# 05_LMS7002M_RF.net
KiCad netlist of a schematic drawn in Altium Designer
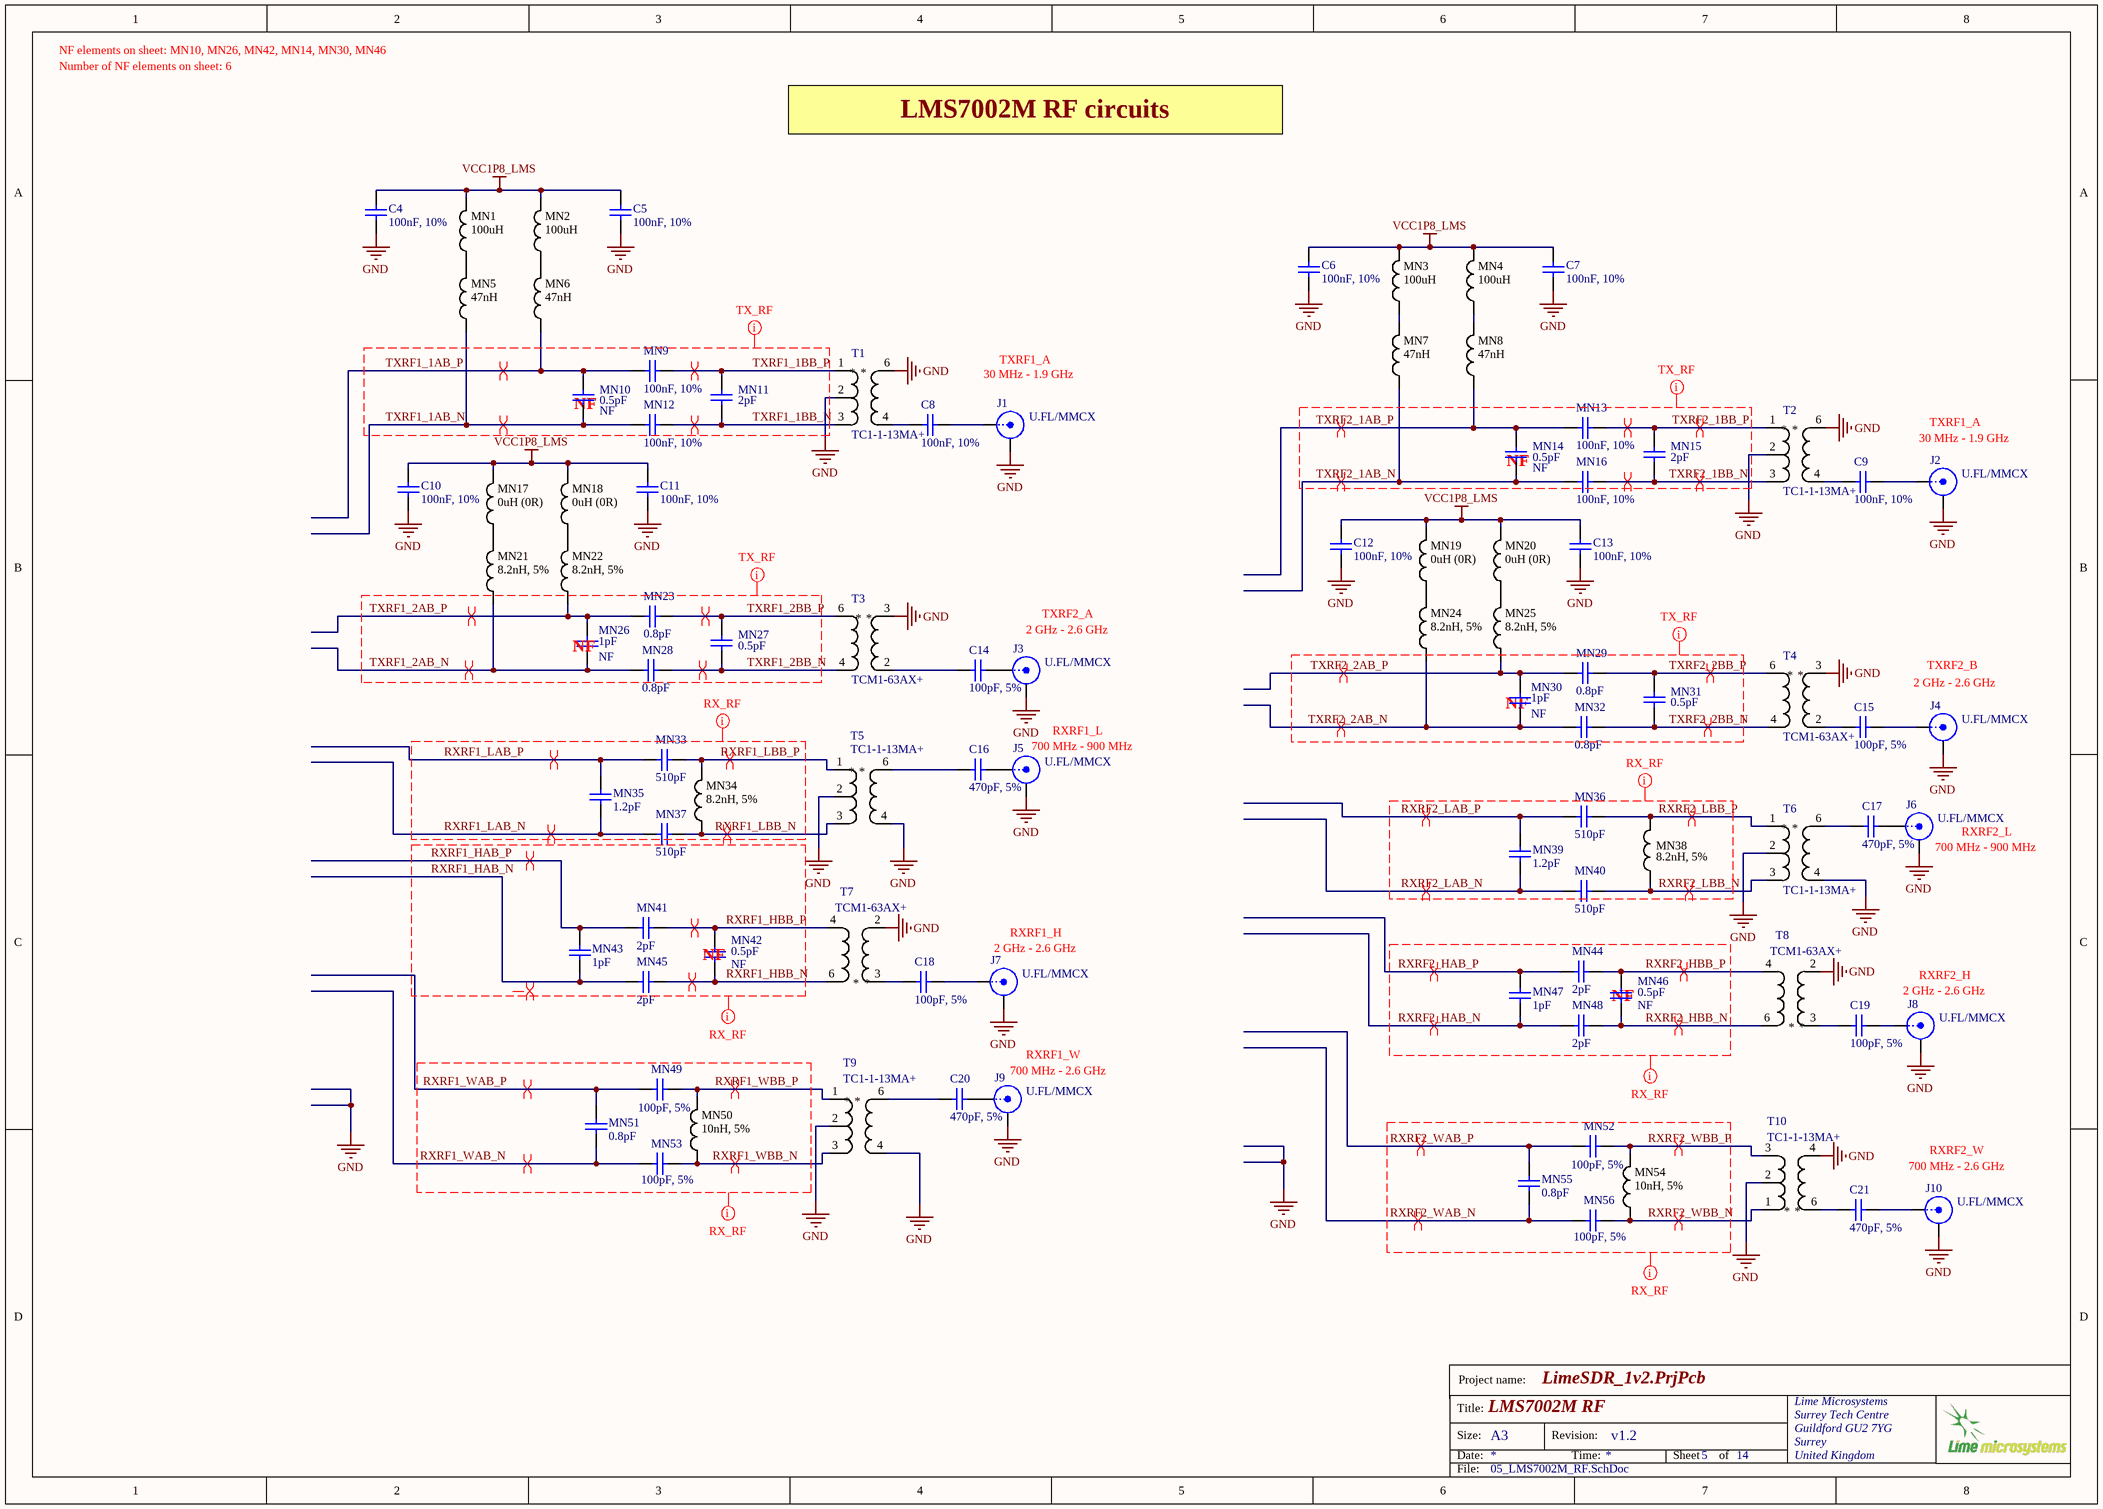
[diagram p0: 05_LMS7002M_RF.SchDoc]

(export (version "E")
  (design (tool "Eeschema 10.0.6"))
  (components
    (comp (ref "C4")
      (value "100nF, 10%")
      (footprint "CAP0402")
      (fields
        (field (name "MANUFACTURER") "Murata Electronics")
        (field (name "TOLERANCE") "10 %")
        (field (name "MANUFACTURER PART NUMBER") "GRM155R71C104KA88D")
      )
      (libsource (lib "LimeMicroAltiumLib_schLib") (part "Cap_0402"))
    )
    (comp (ref "C5")
      (value "100nF, 10%")
      (footprint "CAP0402")
      (fields
        (field (name "MANUFACTURER") "Murata Electronics")
        (field (name "TOLERANCE") "10 %")
        (field (name "MANUFACTURER PART NUMBER") "GRM155R71C104KA88D")
      )
      (libsource (lib "LimeMicroAltiumLib_schLib") (part "Cap_0402"))
    )
    (comp (ref "C6")
      (value "100nF, 10%")
      (footprint "CAP0402")
      (fields
        (field (name "MANUFACTURER") "Murata Electronics")
        (field (name "TOLERANCE") "10 %")
        (field (name "MANUFACTURER PART NUMBER") "GRM155R71C104KA88D")
      )
      (libsource (lib "LimeMicroAltiumLib_schLib") (part "Cap_0402"))
    )
    (comp (ref "C7")
      (value "100nF, 10%")
      (footprint "CAP0402")
      (fields
        (field (name "MANUFACTURER") "Murata Electronics")
        (field (name "TOLERANCE") "10 %")
        (field (name "MANUFACTURER PART NUMBER") "GRM155R71C104KA88D")
      )
      (libsource (lib "LimeMicroAltiumLib_schLib") (part "Cap_0402"))
    )
    (comp (ref "C8")
      (value "100nF, 10%")
      (footprint "CAP0402")
      (fields
        (field (name "MANUFACTURER") "Murata Electronics")
        (field (name "TOLERANCE") "10 %")
        (field (name "MANUFACTURER PART NUMBER") "GRM155R71C104KA88D")
      )
      (libsource (lib "LimeMicroAltiumLib_schLib") (part "Cap_0402"))
    )
    (comp (ref "C9")
      (value "100nF, 10%")
      (footprint "CAP0402")
      (fields
        (field (name "MANUFACTURER") "Murata Electronics")
        (field (name "TOLERANCE") "10 %")
        (field (name "MANUFACTURER PART NUMBER") "GRM155R71C104KA88D")
      )
      (libsource (lib "LimeMicroAltiumLib_schLib") (part "Cap_0402"))
    )
    (comp (ref "C10")
      (value "100nF, 10%")
      (footprint "CAP0402")
      (fields
        (field (name "MANUFACTURER") "Murata Electronics")
        (field (name "TOLERANCE") "10 %")
        (field (name "MANUFACTURER PART NUMBER") "GRM155R71C104KA88D")
      )
      (libsource (lib "LimeMicroAltiumLib_schLib") (part "Cap_0402"))
    )
    (comp (ref "C11")
      (value "100nF, 10%")
      (footprint "CAP0402")
      (fields
        (field (name "MANUFACTURER") "Murata Electronics")
        (field (name "TOLERANCE") "10 %")
        (field (name "MANUFACTURER PART NUMBER") "GRM155R71C104KA88D")
      )
      (libsource (lib "LimeMicroAltiumLib_schLib") (part "Cap_0402"))
    )
    (comp (ref "C12")
      (value "100nF, 10%")
      (footprint "CAP0402")
      (fields
        (field (name "MANUFACTURER") "Murata Electronics")
        (field (name "TOLERANCE") "10 %")
        (field (name "MANUFACTURER PART NUMBER") "GRM155R71C104KA88D")
      )
      (libsource (lib "LimeMicroAltiumLib_schLib") (part "Cap_0402"))
    )
    (comp (ref "C13")
      (value "100nF, 10%")
      (footprint "CAP0402")
      (fields
        (field (name "MANUFACTURER") "Murata Electronics")
        (field (name "TOLERANCE") "10 %")
        (field (name "MANUFACTURER PART NUMBER") "GRM155R71C104KA88D")
      )
      (libsource (lib "LimeMicroAltiumLib_schLib") (part "Cap_0402"))
    )
    (comp (ref "C14")
      (value "100pF, 5%")
      (footprint "CAP0402")
      (fields (field (name "TOLERANCE") "±5%") (field (name "MANUFACTURER") "Yageo"))
      (libsource (lib "LimeMicroAltiumLib_schLib") (part "Cap_0402"))
    )
    (comp (ref "C15")
      (value "100pF, 5%")
      (footprint "CAP0402")
      (fields (field (name "TOLERANCE") "±5%") (field (name "MANUFACTURER") "Yageo"))
      (libsource (lib "LimeMicroAltiumLib_schLib") (part "Cap_0402"))
    )
    (comp (ref "C16")
      (value "470pF, 5%")
      (footprint "CAP0402")
      (fields
        (field (name "MANUFACTURER PART NUMBER") "C1005C0G1H471J050BA")
        (field (name "TOLERANCE") "±5%")
        (field (name "MANUFACTURER") "TDK Corporation")
      )
      (libsource (lib "LimeMicroAltiumLib_schLib") (part "Cap_0402"))
    )
    (comp (ref "C17")
      (value "470pF, 5%")
      (footprint "CAP0402")
      (fields
        (field (name "MANUFACTURER PART NUMBER") "C1005C0G1H471J050BA")
        (field (name "TOLERANCE") "±5%")
        (field (name "MANUFACTURER") "TDK Corporation")
      )
      (libsource (lib "LimeMicroAltiumLib_schLib") (part "Cap_0402"))
    )
    (comp (ref "C18")
      (value "100pF, 5%")
      (footprint "CAP0402")
      (fields (field (name "TOLERANCE") "±5%") (field (name "MANUFACTURER") "Yageo"))
      (libsource (lib "LimeMicroAltiumLib_schLib") (part "Cap_0402"))
    )
    (comp (ref "C19")
      (value "100pF, 5%")
      (footprint "CAP0402")
      (fields (field (name "TOLERANCE") "±5%") (field (name "MANUFACTURER") "Yageo"))
      (libsource (lib "LimeMicroAltiumLib_schLib") (part "Cap_0402"))
    )
    (comp (ref "C20")
      (value "470pF, 5%")
      (footprint "CAP0402")
      (fields
        (field (name "MANUFACTURER PART NUMBER") "C1005C0G1H471J050BA")
        (field (name "TOLERANCE") "±5%")
        (field (name "MANUFACTURER") "TDK Corporation")
      )
      (libsource (lib "LimeMicroAltiumLib_schLib") (part "Cap_0402"))
    )
    (comp (ref "C21")
      (value "470pF, 5%")
      (footprint "CAP0402")
      (fields
        (field (name "MANUFACTURER PART NUMBER") "C1005C0G1H471J050BA")
        (field (name "TOLERANCE") "±5%")
        (field (name "MANUFACTURER") "TDK Corporation")
      )
      (libsource (lib "LimeMicroAltiumLib_schLib") (part "Cap_0402"))
    )
    (comp (ref "J1")
      (value "U.FL/MMCX")
      (footprint "MMCX_UFL_conn_u")
      (description "CONN UMC RCPT STR 50 OHM SMD")
      (fields (field (name "MANUFACTURER") "Molex, LLC"))
      (libsource (lib "LimeMicroAltiumLib_schLib") (part "RF_IF_connector"))
    )
    (comp (ref "J2")
      (value "U.FL/MMCX")
      (footprint "MMCX_UFL_conn_u")
      (description "CONN UMC RCPT STR 50 OHM SMD")
      (fields (field (name "MANUFACTURER") "Molex, LLC"))
      (libsource (lib "LimeMicroAltiumLib_schLib") (part "RF_IF_connector"))
    )
    (comp (ref "J3")
      (value "U.FL/MMCX")
      (footprint "MMCX_UFL_conn_u")
      (description "CONN UMC RCPT STR 50 OHM SMD")
      (fields (field (name "MANUFACTURER") "Molex, LLC"))
      (libsource (lib "LimeMicroAltiumLib_schLib") (part "RF_IF_connector"))
    )
    (comp (ref "J4")
      (value "U.FL/MMCX")
      (footprint "MMCX_UFL_conn_u")
      (description "CONN UMC RCPT STR 50 OHM SMD")
      (fields (field (name "MANUFACTURER") "Molex, LLC"))
      (libsource (lib "LimeMicroAltiumLib_schLib") (part "RF_IF_connector"))
    )
    (comp (ref "J5")
      (value "U.FL/MMCX")
      (footprint "MMCX_UFL_conn_u")
      (description "CONN UMC RCPT STR 50 OHM SMD")
      (fields (field (name "MANUFACTURER") "Molex, LLC"))
      (libsource (lib "LimeMicroAltiumLib_schLib") (part "RF_IF_connector"))
    )
    (comp (ref "J6")
      (value "U.FL/MMCX")
      (footprint "MMCX_UFL_conn_u")
      (description "CONN UMC RCPT STR 50 OHM SMD")
      (fields (field (name "MANUFACTURER") "Molex, LLC"))
      (libsource (lib "LimeMicroAltiumLib_schLib") (part "RF_IF_connector"))
    )
    (comp (ref "J7")
      (value "U.FL/MMCX")
      (footprint "MMCX_UFL_conn_u")
      (description "CONN UMC RCPT STR 50 OHM SMD")
      (fields (field (name "MANUFACTURER") "Molex, LLC"))
      (libsource (lib "LimeMicroAltiumLib_schLib") (part "RF_IF_connector"))
    )
    (comp (ref "J8")
      (value "U.FL/MMCX")
      (footprint "MMCX_UFL_conn_u")
      (description "CONN UMC RCPT STR 50 OHM SMD")
      (fields (field (name "MANUFACTURER") "Molex, LLC"))
      (libsource (lib "LimeMicroAltiumLib_schLib") (part "RF_IF_connector"))
    )
    (comp (ref "J9")
      (value "U.FL/MMCX")
      (footprint "MMCX_UFL_conn_u")
      (description "CONN UMC RCPT STR 50 OHM SMD")
      (fields (field (name "MANUFACTURER") "Molex, LLC"))
      (libsource (lib "LimeMicroAltiumLib_schLib") (part "RF_IF_connector"))
    )
    (comp (ref "J10")
      (value "U.FL/MMCX")
      (footprint "MMCX_UFL_conn_u")
      (description "CONN UMC RCPT STR 50 OHM SMD")
      (fields (field (name "MANUFACTURER") "Molex, LLC"))
      (libsource (lib "LimeMicroAltiumLib_schLib") (part "RF_IF_connector"))
    )
    (comp (ref "MN1")
      (value "100uH")
      (footprint "RES0805")
      (fields
        (field (name "TOLERANCE") "±10%")
        (field (name "MANUFACTURER") "TDK Corporation")
        (field (name "MANUFACTURER PART NUMBER") "MLF2012C101KT000")
      )
      (libsource (lib "LimeMicroAltiumLib_schLib") (part "Inductor_0603"))
    )
    (comp (ref "MN2")
      (value "100uH")
      (footprint "RES0805")
      (fields
        (field (name "TOLERANCE") "±10%")
        (field (name "MANUFACTURER") "TDK Corporation")
        (field (name "MANUFACTURER PART NUMBER") "MLF2012C101KT000")
      )
      (libsource (lib "LimeMicroAltiumLib_schLib") (part "Inductor_0603"))
    )
    (comp (ref "MN3")
      (value "100uH")
      (footprint "RES0805")
      (fields
        (field (name "TOLERANCE") "±10%")
        (field (name "MANUFACTURER") "TDK Corporation")
        (field (name "MANUFACTURER PART NUMBER") "MLF2012C101KT000")
      )
      (libsource (lib "LimeMicroAltiumLib_schLib") (part "Inductor_0603"))
    )
    (comp (ref "MN4")
      (value "100uH")
      (footprint "RES0805")
      (fields
        (field (name "TOLERANCE") "±10%")
        (field (name "MANUFACTURER") "TDK Corporation")
        (field (name "MANUFACTURER PART NUMBER") "MLF2012C101KT000")
      )
      (libsource (lib "LimeMicroAltiumLib_schLib") (part "Inductor_0603"))
    )
    (comp (ref "MN5")
      (value "47nH")
      (footprint "RES0402")
      (fields
        (field (name "MANUFACTURER") "COILCRAFT")
        (field (name "MANUFACTURER PART NUMBER") "0402HP-47NXJLU")
      )
      (libsource (lib "LimeMicroAltiumLib_schLib") (part "Inductor_0603"))
    )
    (comp (ref "MN6")
      (value "47nH")
      (footprint "RES0402")
      (fields
        (field (name "MANUFACTURER") "COILCRAFT")
        (field (name "MANUFACTURER PART NUMBER") "0402HP-47NXJLU")
      )
      (libsource (lib "LimeMicroAltiumLib_schLib") (part "Inductor_0603"))
    )
    (comp (ref "MN7")
      (value "47nH")
      (footprint "RES0402")
      (fields
        (field (name "MANUFACTURER") "COILCRAFT")
        (field (name "MANUFACTURER PART NUMBER") "0402HP-47NXJLU")
      )
      (libsource (lib "LimeMicroAltiumLib_schLib") (part "Inductor_0603"))
    )
    (comp (ref "MN8")
      (value "47nH")
      (footprint "RES0402")
      (fields
        (field (name "MANUFACTURER") "COILCRAFT")
        (field (name "MANUFACTURER PART NUMBER") "0402HP-47NXJLU")
      )
      (libsource (lib "LimeMicroAltiumLib_schLib") (part "Inductor_0603"))
    )
    (comp (ref "MN9")
      (value "100nF, 10%")
      (footprint "CAP0402")
      (fields
        (field (name "MANUFACTURER") "Murata Electronics")
        (field (name "TOLERANCE") "10 %")
        (field (name "MANUFACTURER PART NUMBER") "GRM155R71C104KA88D")
      )
      (libsource (lib "LimeMicroAltiumLib_schLib") (part "Cap_0402"))
    )
    (comp (ref "MN10")
      (value "0.5pF")
      (footprint "CAP0402")
      (fields
        (field (name "ASSEMBLY INFO") "NF")
        (field (name "TOLERANCE") "±0.25pF")
        (field (name "MANUFACTURER") "Yageo")
      )
      (libsource (lib "LimeMicroAltiumLib_schLib") (part "Cap_0402"))
    )
    (comp (ref "MN11")
      (value "2pF")
      (footprint "CAP0402")
      (fields (field (name "MANUFACTURER PART NUMBER") "04025U2R0BAT2A") (field (name "MANUFACTURER") "AVX"))
      (libsource (lib "LimeMicroAltiumLib_schLib") (part "Cap_0402"))
    )
    (comp (ref "MN12")
      (value "100nF, 10%")
      (footprint "CAP0402")
      (fields
        (field (name "MANUFACTURER") "Murata Electronics")
        (field (name "TOLERANCE") "10 %")
        (field (name "MANUFACTURER PART NUMBER") "GRM155R71C104KA88D")
      )
      (libsource (lib "LimeMicroAltiumLib_schLib") (part "Cap_0402"))
    )
    (comp (ref "MN13")
      (value "100nF, 10%")
      (footprint "CAP0402")
      (fields
        (field (name "MANUFACTURER") "Murata Electronics")
        (field (name "TOLERANCE") "10 %")
        (field (name "MANUFACTURER PART NUMBER") "GRM155R71C104KA88D")
      )
      (libsource (lib "LimeMicroAltiumLib_schLib") (part "Cap_0402"))
    )
    (comp (ref "MN14")
      (value "0.5pF")
      (footprint "CAP0402")
      (fields
        (field (name "ASSEMBLY INFO") "NF")
        (field (name "TOLERANCE") "±0.25pF")
        (field (name "MANUFACTURER") "Yageo")
      )
      (libsource (lib "LimeMicroAltiumLib_schLib") (part "Cap_0402"))
    )
    (comp (ref "MN15")
      (value "2pF")
      (footprint "CAP0402")
      (fields (field (name "MANUFACTURER PART NUMBER") "04025U2R0BAT2A") (field (name "MANUFACTURER") "AVX"))
      (libsource (lib "LimeMicroAltiumLib_schLib") (part "Cap_0402"))
    )
    (comp (ref "MN16")
      (value "100nF, 10%")
      (footprint "CAP0402")
      (fields
        (field (name "MANUFACTURER") "Murata Electronics")
        (field (name "TOLERANCE") "10 %")
        (field (name "MANUFACTURER PART NUMBER") "GRM155R71C104KA88D")
      )
      (libsource (lib "LimeMicroAltiumLib_schLib") (part "Cap_0402"))
    )
    (comp (ref "MN17")
      (value "0uH (0R)")
      (footprint "RES0805")
      (fields (field (name "MANUFACTURER") "BOURNS"))
      (libsource (lib "LimeMicroAltiumLib_schLib") (part "Inductor_0603"))
    )
    (comp (ref "MN18")
      (value "0uH (0R)")
      (footprint "RES0805")
      (fields (field (name "MANUFACTURER") "BOURNS"))
      (libsource (lib "LimeMicroAltiumLib_schLib") (part "Inductor_0603"))
    )
    (comp (ref "MN19")
      (value "0uH (0R)")
      (footprint "RES0805")
      (fields (field (name "MANUFACTURER") "BOURNS"))
      (libsource (lib "LimeMicroAltiumLib_schLib") (part "Inductor_0603"))
    )
    (comp (ref "MN20")
      (value "0uH (0R)")
      (footprint "RES0805")
      (fields (field (name "MANUFACTURER") "BOURNS"))
      (libsource (lib "LimeMicroAltiumLib_schLib") (part "Inductor_0603"))
    )
    (comp (ref "MN21")
      (value "8.2nH, 5%")
      (footprint "RES0402")
      (fields (field (name "MANUFACTURER") "COILCRAFT"))
      (libsource (lib "LimeMicroAltiumLib_schLib") (part "Inductor_0603"))
    )
    (comp (ref "MN22")
      (value "8.2nH, 5%")
      (footprint "RES0402")
      (fields (field (name "MANUFACTURER") "COILCRAFT"))
      (libsource (lib "LimeMicroAltiumLib_schLib") (part "Inductor_0603"))
    )
    (comp (ref "MN23")
      (value "0.8pF")
      (footprint "CAP0402")
      (fields
        (field (name "TOLERANCE") "±0.1pF")
        (field (name "MANUFACTURER") "Murata Electronics North America")
        (field (name "MANUFACTURER PART NUMBER") "GRM1555C1HR80BA01D")
      )
      (libsource (lib "LimeMicroAltiumLib_schLib") (part "Cap_0402"))
    )
    (comp (ref "MN24")
      (value "8.2nH, 5%")
      (footprint "RES0402")
      (fields (field (name "MANUFACTURER") "COILCRAFT"))
      (libsource (lib "LimeMicroAltiumLib_schLib") (part "Inductor_0603"))
    )
    (comp (ref "MN25")
      (value "8.2nH, 5%")
      (footprint "RES0402")
      (fields (field (name "MANUFACTURER") "COILCRAFT"))
      (libsource (lib "LimeMicroAltiumLib_schLib") (part "Inductor_0603"))
    )
    (comp (ref "MN26")
      (value "1pF")
      (footprint "CAP0402")
      (fields
        (field (name "ASSEMBLY INFO") "NF")
        (field (name "MANUFACTURER") "TDK Corporation")
        (field (name "TOLERANCE") "±0.1pF")
      )
      (libsource (lib "LimeMicroAltiumLib_schLib") (part "Cap_0402"))
    )
    (comp (ref "MN27")
      (value "0.5pF")
      (footprint "CAP0402")
      (fields (field (name "TOLERANCE") "±0.25pF") (field (name "MANUFACTURER") "Yageo"))
      (libsource (lib "LimeMicroAltiumLib_schLib") (part "Cap_0402"))
    )
    (comp (ref "MN28")
      (value "0.8pF")
      (footprint "CAP0402")
      (fields
        (field (name "TOLERANCE") "±0.1pF")
        (field (name "MANUFACTURER") "Murata Electronics North America")
        (field (name "MANUFACTURER PART NUMBER") "GRM1555C1HR80BA01D")
      )
      (libsource (lib "LimeMicroAltiumLib_schLib") (part "Cap_0402"))
    )
    (comp (ref "MN29")
      (value "0.8pF")
      (footprint "CAP0402")
      (fields
        (field (name "TOLERANCE") "±0.1pF")
        (field (name "MANUFACTURER") "Murata Electronics North America")
        (field (name "MANUFACTURER PART NUMBER") "GRM1555C1HR80BA01D")
      )
      (libsource (lib "LimeMicroAltiumLib_schLib") (part "Cap_0402"))
    )
    (comp (ref "MN30")
      (value "1pF")
      (footprint "CAP0402")
      (fields
        (field (name "ASSEMBLY INFO") "NF")
        (field (name "MANUFACTURER") "TDK Corporation")
        (field (name "TOLERANCE") "±0.1pF")
      )
      (libsource (lib "LimeMicroAltiumLib_schLib") (part "Cap_0402"))
    )
    (comp (ref "MN31")
      (value "0.5pF")
      (footprint "CAP0402")
      (fields (field (name "TOLERANCE") "±0.25pF") (field (name "MANUFACTURER") "Yageo"))
      (libsource (lib "LimeMicroAltiumLib_schLib") (part "Cap_0402"))
    )
    (comp (ref "MN32")
      (value "0.8pF")
      (footprint "CAP0402")
      (fields
        (field (name "TOLERANCE") "±0.1pF")
        (field (name "MANUFACTURER") "Murata Electronics North America")
        (field (name "MANUFACTURER PART NUMBER") "GRM1555C1HR80BA01D")
      )
      (libsource (lib "LimeMicroAltiumLib_schLib") (part "Cap_0402"))
    )
    (comp (ref "MN33")
      (value "510pF")
      (footprint "CAP0402")
      (fields
        (field (name "TOLERANCE") "±5%")
        (field (name "MANUFACTURER") "Murata Electronics North America")
        (field (name "MANUFACTURER PART NUMBER") "GRM1555C1H511JA01D")
      )
      (libsource (lib "LimeMicroAltiumLib_schLib") (part "Cap_0402"))
    )
    (comp (ref "MN34")
      (value "8.2nH, 5%")
      (footprint "RES0402")
      (fields (field (name "MANUFACTURER") "COILCRAFT"))
      (libsource (lib "LimeMicroAltiumLib_schLib") (part "Inductor_0603"))
    )
    (comp (ref "MN35")
      (value "1.2pF")
      (footprint "CAP0402")
      (fields
        (field (name "MANUFACTURER") "Murata Electronics North America")
        (field (name "MANUFACTURER PART NUMBER") "GRM1555C1H1R2CA01D")
        (field (name "TOLERANCE") "±0.25pF")
      )
      (libsource (lib "LimeMicroAltiumLib_schLib") (part "Cap_0402"))
    )
    (comp (ref "MN36")
      (value "510pF")
      (footprint "CAP0402")
      (fields
        (field (name "TOLERANCE") "±5%")
        (field (name "MANUFACTURER") "Murata Electronics North America")
        (field (name "MANUFACTURER PART NUMBER") "GRM1555C1H511JA01D")
      )
      (libsource (lib "LimeMicroAltiumLib_schLib") (part "Cap_0402"))
    )
    (comp (ref "MN37")
      (value "510pF")
      (footprint "CAP0402")
      (fields
        (field (name "TOLERANCE") "±5%")
        (field (name "MANUFACTURER") "Murata Electronics North America")
        (field (name "MANUFACTURER PART NUMBER") "GRM1555C1H511JA01D")
      )
      (libsource (lib "LimeMicroAltiumLib_schLib") (part "Cap_0402"))
    )
    (comp (ref "MN38")
      (value "8.2nH, 5%")
      (footprint "RES0402")
      (fields (field (name "MANUFACTURER") "COILCRAFT"))
      (libsource (lib "LimeMicroAltiumLib_schLib") (part "Inductor_0603"))
    )
    (comp (ref "MN39")
      (value "1.2pF")
      (footprint "CAP0402")
      (fields
        (field (name "MANUFACTURER") "Murata Electronics North America")
        (field (name "MANUFACTURER PART NUMBER") "GRM1555C1H1R2CA01D")
        (field (name "TOLERANCE") "±0.25pF")
      )
      (libsource (lib "LimeMicroAltiumLib_schLib") (part "Cap_0402"))
    )
    (comp (ref "MN40")
      (value "510pF")
      (footprint "CAP0402")
      (fields
        (field (name "TOLERANCE") "±5%")
        (field (name "MANUFACTURER") "Murata Electronics North America")
        (field (name "MANUFACTURER PART NUMBER") "GRM1555C1H511JA01D")
      )
      (libsource (lib "LimeMicroAltiumLib_schLib") (part "Cap_0402"))
    )
    (comp (ref "MN41")
      (value "2pF")
      (footprint "CAP0402")
      (fields (field (name "MANUFACTURER PART NUMBER") "04025U2R0BAT2A") (field (name "MANUFACTURER") "AVX"))
      (libsource (lib "LimeMicroAltiumLib_schLib") (part "Cap_0402"))
    )
    (comp (ref "MN42")
      (value "0.5pF")
      (footprint "CAP0402")
      (fields
        (field (name "ASSEMBLY INFO") "NF")
        (field (name "TOLERANCE") "±0.25pF")
        (field (name "MANUFACTURER") "Yageo")
      )
      (libsource (lib "LimeMicroAltiumLib_schLib") (part "Cap_0402"))
    )
    (comp (ref "MN43")
      (value "1pF")
      (footprint "CAP0402")
      (fields (field (name "MANUFACTURER") "TDK Corporation") (field (name "TOLERANCE") "±0.1pF"))
      (libsource (lib "LimeMicroAltiumLib_schLib") (part "Cap_0402"))
    )
    (comp (ref "MN44")
      (value "2pF")
      (footprint "CAP0402")
      (fields (field (name "MANUFACTURER PART NUMBER") "04025U2R0BAT2A") (field (name "MANUFACTURER") "AVX"))
      (libsource (lib "LimeMicroAltiumLib_schLib") (part "Cap_0402"))
    )
    (comp (ref "MN45")
      (value "2pF")
      (footprint "CAP0402")
      (fields (field (name "MANUFACTURER PART NUMBER") "04025U2R0BAT2A") (field (name "MANUFACTURER") "AVX"))
      (libsource (lib "LimeMicroAltiumLib_schLib") (part "Cap_0402"))
    )
    (comp (ref "MN46")
      (value "0.5pF")
      (footprint "CAP0402")
      (fields
        (field (name "ASSEMBLY INFO") "NF")
        (field (name "TOLERANCE") "±0.25pF")
        (field (name "MANUFACTURER") "Yageo")
      )
      (libsource (lib "LimeMicroAltiumLib_schLib") (part "Cap_0402"))
    )
    (comp (ref "MN47")
      (value "1pF")
      (footprint "CAP0402")
      (fields (field (name "MANUFACTURER") "TDK Corporation") (field (name "TOLERANCE") "±0.1pF"))
      (libsource (lib "LimeMicroAltiumLib_schLib") (part "Cap_0402"))
    )
    (comp (ref "MN48")
      (value "2pF")
      (footprint "CAP0402")
      (fields (field (name "MANUFACTURER PART NUMBER") "04025U2R0BAT2A") (field (name "MANUFACTURER") "AVX"))
      (libsource (lib "LimeMicroAltiumLib_schLib") (part "Cap_0402"))
    )
    (comp (ref "MN49")
      (value "100pF, 5%")
      (footprint "CAP0402")
      (fields (field (name "TOLERANCE") "±5%") (field (name "MANUFACTURER") "Yageo"))
      (libsource (lib "LimeMicroAltiumLib_schLib") (part "Cap_0402"))
    )
    (comp (ref "MN50")
      (value "10nH, 5%")
      (footprint "RES0402")
      (fields (field (name "MANUFACTURER") "COILCRAFT"))
      (libsource (lib "LimeMicroAltiumLib_schLib") (part "Inductor_0603"))
    )
    (comp (ref "MN51")
      (value "0.8pF")
      (footprint "CAP0402")
      (fields
        (field (name "TOLERANCE") "±0.1pF")
        (field (name "MANUFACTURER") "Murata Electronics North America")
        (field (name "MANUFACTURER PART NUMBER") "GRM1555C1HR80BA01D")
      )
      (libsource (lib "LimeMicroAltiumLib_schLib") (part "Cap_0402"))
    )
    (comp (ref "MN52")
      (value "100pF, 5%")
      (footprint "CAP0402")
      (fields (field (name "TOLERANCE") "±5%") (field (name "MANUFACTURER") "Yageo"))
      (libsource (lib "LimeMicroAltiumLib_schLib") (part "Cap_0402"))
    )
    (comp (ref "MN53")
      (value "100pF, 5%")
      (footprint "CAP0402")
      (fields (field (name "TOLERANCE") "±5%") (field (name "MANUFACTURER") "Yageo"))
      (libsource (lib "LimeMicroAltiumLib_schLib") (part "Cap_0402"))
    )
    (comp (ref "MN54")
      (value "10nH, 5%")
      (footprint "RES0402")
      (fields (field (name "MANUFACTURER") "COILCRAFT"))
      (libsource (lib "LimeMicroAltiumLib_schLib") (part "Inductor_0603"))
    )
    (comp (ref "MN55")
      (value "0.8pF")
      (footprint "CAP0402")
      (fields
        (field (name "TOLERANCE") "±0.1pF")
        (field (name "MANUFACTURER") "Murata Electronics North America")
        (field (name "MANUFACTURER PART NUMBER") "GRM1555C1HR80BA01D")
      )
      (libsource (lib "LimeMicroAltiumLib_schLib") (part "Cap_0402"))
    )
    (comp (ref "MN56")
      (value "100pF, 5%")
      (footprint "CAP0402")
      (fields (field (name "TOLERANCE") "±5%") (field (name "MANUFACTURER") "Yageo"))
      (libsource (lib "LimeMicroAltiumLib_schLib") (part "Cap_0402"))
    )
    (comp (ref "T1")
      (value "TC1-1-13MA+")
      (footprint "TC1-1-13MA+_v2")
      (fields (field (name "MANUFACTURER") "Mini-Circuits"))
      (libsource (lib "LimeMicroAltiumLib_schLib") (part "Balun"))
    )
    (comp (ref "T2")
      (value "TC1-1-13MA+")
      (footprint "TC1-1-13MA+_v2")
      (fields (field (name "MANUFACTURER") "Mini-Circuits"))
      (libsource (lib "LimeMicroAltiumLib_schLib") (part "Balun"))
    )
    (comp (ref "T3")
      (value "TCM1-63AX+")
      (footprint "TCM1-63AX+_v2")
      (fields (field (name "MANUFACTURER") "Mini-circuits"))
      (libsource (lib "") (part "Balun_v2_1"))
    )
    (comp (ref "T4")
      (value "TCM1-63AX+")
      (footprint "TCM1-63AX+_v2")
      (fields (field (name "MANUFACTURER") "Mini-circuits"))
      (libsource (lib "") (part "Balun_v2_1"))
    )
    (comp (ref "T5")
      (value "TC1-1-13MA+")
      (footprint "TC1-1-13MA+_v2")
      (fields (field (name "MANUFACTURER") "Mini-Circuits"))
      (libsource (lib "LimeMicroAltiumLib_schLib") (part "Balun"))
    )
    (comp (ref "T6")
      (value "TC1-1-13MA+")
      (footprint "TC1-1-13MA+_v2")
      (fields (field (name "MANUFACTURER") "Mini-Circuits"))
      (libsource (lib "LimeMicroAltiumLib_schLib") (part "Balun"))
    )
    (comp (ref "T7")
      (value "TCM1-63AX+")
      (footprint "TCM1-63AX+_v2")
      (fields (field (name "MANUFACTURER") "Mini-circuits"))
      (libsource (lib "LimeMicroAltiumLib_schLib") (part "Balun_v2"))
    )
    (comp (ref "T8")
      (value "TCM1-63AX+")
      (footprint "TCM1-63AX+_v2")
      (fields (field (name "MANUFACTURER") "Mini-circuits"))
      (libsource (lib "LimeMicroAltiumLib_schLib") (part "Balun_v2"))
    )
    (comp (ref "T9")
      (value "TC1-1-13MA+")
      (footprint "TC1-1-13MA+_v2")
      (fields (field (name "MANUFACTURER") "Mini-Circuits"))
      (libsource (lib "LimeMicroAltiumLib_schLib") (part "Balun"))
    )
    (comp (ref "T10")
      (value "TC1-1-13MA+")
      (footprint "TC1-1-13MA+_v2")
      (fields (field (name "MANUFACTURER") "Mini-Circuits"))
      (libsource (lib "") (part "Balun_1"))
    )
  )
  (nets
    (net (code "1") (name "/RXRF1_HAB_N") (class "Default")
      (node (ref "MN43") (pin "1") (pinfunction "1_1") (pintype "passive"))
      (node (ref "MN45") (pin "2") (pinfunction "2_2") (pintype "passive"))
    )
    (net (code "2") (name "/RXRF1_HAB_P") (class "Default")
      (node (ref "MN41") (pin "2") (pinfunction "2_2") (pintype "passive"))
      (node (ref "MN43") (pin "2") (pinfunction "2_2") (pintype "passive"))
    )
    (net (code "3") (name "/RXRF1_HBB_N") (class "Default")
      (node (ref "MN42") (pin "1") (pinfunction "1_1") (pintype "passive"))
      (node (ref "MN45") (pin "1") (pinfunction "1_1") (pintype "passive"))
      (node (ref "T7") (pin "6") (pinfunction "6_6") (pintype "passive"))
    )
    (net (code "4") (name "/RXRF1_HBB_P") (class "Default")
      (node (ref "MN41") (pin "1") (pinfunction "1_1") (pintype "passive"))
      (node (ref "MN42") (pin "2") (pinfunction "2_2") (pintype "passive"))
      (node (ref "T7") (pin "4") (pinfunction "4_4") (pintype "passive"))
    )
    (net (code "5") (name "/RXRF1_LAB_N") (class "Default")
      (node (ref "MN35") (pin "1") (pinfunction "1_1") (pintype "passive"))
      (node (ref "MN37") (pin "2") (pinfunction "2_2") (pintype "passive"))
    )
    (net (code "6") (name "/RXRF1_LAB_P") (class "Default")
      (node (ref "MN33") (pin "2") (pinfunction "2_2") (pintype "passive"))
      (node (ref "MN35") (pin "2") (pinfunction "2_2") (pintype "passive"))
    )
    (net (code "7") (name "/RXRF1_LBB_N") (class "Default")
      (node (ref "MN34") (pin "1") (pinfunction "1_1") (pintype "passive"))
      (node (ref "MN37") (pin "1") (pinfunction "1_1") (pintype "passive"))
      (node (ref "T5") (pin "3") (pinfunction "3_3") (pintype "passive"))
    )
    (net (code "8") (name "/RXRF1_LBB_P") (class "Default")
      (node (ref "MN33") (pin "1") (pinfunction "1_1") (pintype "passive"))
      (node (ref "MN34") (pin "2") (pinfunction "2_2") (pintype "passive"))
      (node (ref "T5") (pin "1") (pinfunction "1_1") (pintype "passive"))
    )
    (net (code "9") (name "/RXRF1_WAB_N") (class "Default")
      (node (ref "MN51") (pin "2") (pinfunction "2_2") (pintype "passive"))
      (node (ref "MN53") (pin "2") (pinfunction "2_2") (pintype "passive"))
    )
    (net (code "10") (name "/RXRF1_WAB_P") (class "Default")
      (node (ref "MN49") (pin "2") (pinfunction "2_2") (pintype "passive"))
      (node (ref "MN51") (pin "1") (pinfunction "1_1") (pintype "passive"))
    )
    (net (code "11") (name "/RXRF1_WBB_N") (class "Default")
      (node (ref "MN50") (pin "1") (pinfunction "1_1") (pintype "passive"))
      (node (ref "MN53") (pin "1") (pinfunction "1_1") (pintype "passive"))
      (node (ref "T9") (pin "3") (pinfunction "3_3") (pintype "passive"))
    )
    (net (code "12") (name "/RXRF1_WBB_P") (class "Default")
      (node (ref "MN49") (pin "1") (pinfunction "1_1") (pintype "passive"))
      (node (ref "MN50") (pin "2") (pinfunction "2_2") (pintype "passive"))
      (node (ref "T9") (pin "1") (pinfunction "1_1") (pintype "passive"))
    )
    (net (code "13") (name "/RXRF2_HAB_N") (class "Default")
      (node (ref "MN47") (pin "1") (pinfunction "1_1") (pintype "passive"))
      (node (ref "MN48") (pin "2") (pinfunction "2_2") (pintype "passive"))
    )
    (net (code "14") (name "/RXRF2_HAB_P") (class "Default")
      (node (ref "MN44") (pin "2") (pinfunction "2_2") (pintype "passive"))
      (node (ref "MN47") (pin "2") (pinfunction "2_2") (pintype "passive"))
    )
    (net (code "15") (name "/RXRF2_HBB_N") (class "Default")
      (node (ref "MN46") (pin "1") (pinfunction "1_1") (pintype "passive"))
      (node (ref "MN48") (pin "1") (pinfunction "1_1") (pintype "passive"))
      (node (ref "T8") (pin "6") (pinfunction "6_6") (pintype "passive"))
    )
    (net (code "16") (name "/RXRF2_HBB_P") (class "Default")
      (node (ref "MN44") (pin "1") (pinfunction "1_1") (pintype "passive"))
      (node (ref "MN46") (pin "2") (pinfunction "2_2") (pintype "passive"))
      (node (ref "T8") (pin "4") (pinfunction "4_4") (pintype "passive"))
    )
    (net (code "17") (name "/RXRF2_LAB_N") (class "Default")
      (node (ref "MN39") (pin "1") (pinfunction "1_1") (pintype "passive"))
      (node (ref "MN40") (pin "2") (pinfunction "2_2") (pintype "passive"))
    )
    (net (code "18") (name "/RXRF2_LAB_P") (class "Default")
      (node (ref "MN36") (pin "2") (pinfunction "2_2") (pintype "passive"))
      (node (ref "MN39") (pin "2") (pinfunction "2_2") (pintype "passive"))
    )
    (net (code "19") (name "/RXRF2_LBB_N") (class "Default")
      (node (ref "MN38") (pin "1") (pinfunction "1_1") (pintype "passive"))
      (node (ref "MN40") (pin "1") (pinfunction "1_1") (pintype "passive"))
      (node (ref "T6") (pin "3") (pinfunction "3_3") (pintype "passive"))
    )
    (net (code "20") (name "/RXRF2_LBB_P") (class "Default")
      (node (ref "MN36") (pin "1") (pinfunction "1_1") (pintype "passive"))
      (node (ref "MN38") (pin "2") (pinfunction "2_2") (pintype "passive"))
      (node (ref "T6") (pin "1") (pinfunction "1_1") (pintype "passive"))
    )
    (net (code "21") (name "/RXRF2_WAB_N") (class "Default")
      (node (ref "MN55") (pin "2") (pinfunction "2_2") (pintype "passive"))
      (node (ref "MN56") (pin "2") (pinfunction "2_2") (pintype "passive"))
    )
    (net (code "22") (name "/RXRF2_WAB_P") (class "Default")
      (node (ref "MN52") (pin "2") (pinfunction "2_2") (pintype "passive"))
      (node (ref "MN55") (pin "1") (pinfunction "1_1") (pintype "passive"))
    )
    (net (code "23") (name "/RXRF2_WBB_N") (class "Default")
      (node (ref "MN54") (pin "1") (pinfunction "1_1") (pintype "passive"))
      (node (ref "MN56") (pin "1") (pinfunction "1_1") (pintype "passive"))
      (node (ref "T10") (pin "1") (pinfunction "1_1") (pintype "passive"))
    )
    (net (code "24") (name "/RXRF2_WBB_P") (class "Default")
      (node (ref "MN52") (pin "1") (pinfunction "1_1") (pintype "passive"))
      (node (ref "MN54") (pin "2") (pinfunction "2_2") (pintype "passive"))
      (node (ref "T10") (pin "3") (pinfunction "3_3") (pintype "passive"))
    )
    (net (code "25") (name "/TXRF1_1AB_N") (class "Default")
      (node (ref "MN10") (pin "1") (pinfunction "1_1") (pintype "passive"))
      (node (ref "MN12") (pin "1") (pinfunction "1_1") (pintype "passive"))
      (node (ref "MN5") (pin "1") (pinfunction "1_1") (pintype "passive"))
    )
    (net (code "26") (name "/TXRF1_1AB_P") (class "Default")
      (node (ref "MN10") (pin "2") (pinfunction "2_2") (pintype "passive"))
      (node (ref "MN6") (pin "1") (pinfunction "1_1") (pintype "passive"))
      (node (ref "MN9") (pin "2") (pinfunction "2_2") (pintype "passive"))
    )
    (net (code "27") (name "/TXRF1_1BB_N") (class "Default")
      (node (ref "MN11") (pin "1") (pinfunction "1_1") (pintype "passive"))
      (node (ref "MN12") (pin "2") (pinfunction "2_2") (pintype "passive"))
      (node (ref "T1") (pin "3") (pinfunction "3_3") (pintype "passive"))
    )
    (net (code "28") (name "/TXRF1_1BB_P") (class "Default")
      (node (ref "MN11") (pin "2") (pinfunction "2_2") (pintype "passive"))
      (node (ref "MN9") (pin "1") (pinfunction "1_1") (pintype "passive"))
      (node (ref "T1") (pin "1") (pinfunction "1_1") (pintype "passive"))
    )
    (net (code "29") (name "/TXRF1_2AB_N") (class "Default")
      (node (ref "MN21") (pin "1") (pinfunction "1_1") (pintype "passive"))
      (node (ref "MN26") (pin "2") (pinfunction "2_2") (pintype "passive"))
      (node (ref "MN28") (pin "2") (pinfunction "2_2") (pintype "passive"))
    )
    (net (code "30") (name "/TXRF1_2AB_P") (class "Default")
      (node (ref "MN22") (pin "1") (pinfunction "1_1") (pintype "passive"))
      (node (ref "MN23") (pin "2") (pinfunction "2_2") (pintype "passive"))
      (node (ref "MN26") (pin "1") (pinfunction "1_1") (pintype "passive"))
    )
    (net (code "31") (name "/TXRF1_2BB_N") (class "Default")
      (node (ref "MN27") (pin "1") (pinfunction "1_1") (pintype "passive"))
      (node (ref "MN28") (pin "1") (pinfunction "1_1") (pintype "passive"))
      (node (ref "T3") (pin "4") (pinfunction "4_4") (pintype "passive"))
    )
    (net (code "32") (name "/TXRF1_2BB_P") (class "Default")
      (node (ref "MN23") (pin "1") (pinfunction "1_1") (pintype "passive"))
      (node (ref "MN27") (pin "2") (pinfunction "2_2") (pintype "passive"))
      (node (ref "T3") (pin "6") (pinfunction "6_6") (pintype "passive"))
    )
    (net (code "33") (name "/TXRF2_1AB_N") (class "Default")
      (node (ref "MN14") (pin "1") (pinfunction "1_1") (pintype "passive"))
      (node (ref "MN16") (pin "1") (pinfunction "1_1") (pintype "passive"))
      (node (ref "MN7") (pin "1") (pinfunction "1_1") (pintype "passive"))
    )
    (net (code "34") (name "/TXRF2_1AB_P") (class "Default")
      (node (ref "MN13") (pin "2") (pinfunction "2_2") (pintype "passive"))
      (node (ref "MN14") (pin "2") (pinfunction "2_2") (pintype "passive"))
      (node (ref "MN8") (pin "1") (pinfunction "1_1") (pintype "passive"))
    )
    (net (code "35") (name "/TXRF2_1BB_N") (class "Default")
      (node (ref "MN15") (pin "1") (pinfunction "1_1") (pintype "passive"))
      (node (ref "MN16") (pin "2") (pinfunction "2_2") (pintype "passive"))
      (node (ref "T2") (pin "3") (pinfunction "3_3") (pintype "passive"))
    )
    (net (code "36") (name "/TXRF2_1BB_P") (class "Default")
      (node (ref "MN13") (pin "1") (pinfunction "1_1") (pintype "passive"))
      (node (ref "MN15") (pin "2") (pinfunction "2_2") (pintype "passive"))
      (node (ref "T2") (pin "1") (pinfunction "1_1") (pintype "passive"))
    )
    (net (code "37") (name "/TXRF2_2AB_N") (class "Default")
      (node (ref "MN24") (pin "1") (pinfunction "1_1") (pintype "passive"))
      (node (ref "MN30") (pin "2") (pinfunction "2_2") (pintype "passive"))
      (node (ref "MN32") (pin "2") (pinfunction "2_2") (pintype "passive"))
    )
    (net (code "38") (name "/TXRF2_2AB_P") (class "Default")
      (node (ref "MN25") (pin "1") (pinfunction "1_1") (pintype "passive"))
      (node (ref "MN29") (pin "2") (pinfunction "2_2") (pintype "passive"))
      (node (ref "MN30") (pin "1") (pinfunction "1_1") (pintype "passive"))
    )
    (net (code "39") (name "/TXRF2_2BB_N") (class "Default")
      (node (ref "MN31") (pin "1") (pinfunction "1_1") (pintype "passive"))
      (node (ref "MN32") (pin "1") (pinfunction "1_1") (pintype "passive"))
      (node (ref "T4") (pin "4") (pinfunction "4_4") (pintype "passive"))
    )
    (net (code "40") (name "/TXRF2_2BB_P") (class "Default")
      (node (ref "MN29") (pin "1") (pinfunction "1_1") (pintype "passive"))
      (node (ref "MN31") (pin "2") (pinfunction "2_2") (pintype "passive"))
      (node (ref "T4") (pin "6") (pinfunction "6_6") (pintype "passive"))
    )
    (net (code "41") (name "GND") (class "Default")
      (node (ref "C10") (pin "1") (pinfunction "1_1") (pintype "passive"))
      (node (ref "C11") (pin "1") (pinfunction "1_1") (pintype "passive"))
      (node (ref "C12") (pin "1") (pinfunction "1_1") (pintype "passive"))
      (node (ref "C13") (pin "1") (pinfunction "1_1") (pintype "passive"))
      (node (ref "C4") (pin "1") (pinfunction "1_1") (pintype "passive"))
      (node (ref "C5") (pin "1") (pinfunction "1_1") (pintype "passive"))
      (node (ref "C6") (pin "1") (pinfunction "1_1") (pintype "passive"))
      (node (ref "C7") (pin "1") (pinfunction "1_1") (pintype "passive"))
      (node (ref "J1") (pin "2") (pinfunction "Y_2") (pintype "passive"))
      (node (ref "J10") (pin "2") (pinfunction "Y_2") (pintype "passive"))
      (node (ref "J2") (pin "2") (pinfunction "Y_2") (pintype "passive"))
      (node (ref "J3") (pin "2") (pinfunction "Y_2") (pintype "passive"))
      (node (ref "J4") (pin "2") (pinfunction "Y_2") (pintype "passive"))
      (node (ref "J5") (pin "2") (pinfunction "Y_2") (pintype "passive"))
      (node (ref "J6") (pin "2") (pinfunction "Y_2") (pintype "passive"))
      (node (ref "J7") (pin "2") (pinfunction "Y_2") (pintype "passive"))
      (node (ref "J8") (pin "2") (pinfunction "Y_2") (pintype "passive"))
      (node (ref "J9") (pin "2") (pinfunction "Y_2") (pintype "passive"))
      (node (ref "T1") (pin "2") (pinfunction "2_2") (pintype "passive"))
      (node (ref "T1") (pin "6") (pinfunction "6_6") (pintype "passive"))
      (node (ref "T10") (pin "2") (pinfunction "2_2") (pintype "passive"))
      (node (ref "T10") (pin "4") (pinfunction "4_4") (pintype "passive"))
      (node (ref "T2") (pin "2") (pinfunction "2_2") (pintype "passive"))
      (node (ref "T2") (pin "6") (pinfunction "6_6") (pintype "passive"))
      (node (ref "T3") (pin "3") (pinfunction "3_3") (pintype "passive"))
      (node (ref "T4") (pin "3") (pinfunction "3_3") (pintype "passive"))
      (node (ref "T5") (pin "2") (pinfunction "2_2") (pintype "passive"))
      (node (ref "T5") (pin "4") (pinfunction "4_4") (pintype "passive"))
      (node (ref "T6") (pin "2") (pinfunction "2_2") (pintype "passive"))
      (node (ref "T6") (pin "4") (pinfunction "4_4") (pintype "passive"))
      (node (ref "T7") (pin "2") (pinfunction "2_2") (pintype "passive"))
      (node (ref "T8") (pin "2") (pinfunction "2_2") (pintype "passive"))
      (node (ref "T9") (pin "2") (pinfunction "2_2") (pintype "passive"))
      (node (ref "T9") (pin "4") (pinfunction "4_4") (pintype "passive"))
    )
    (net (code "42") (name "Net-(C8-Pad2)") (class "Default")
      (node (ref "C8") (pin "2") (pinfunction "2_2") (pintype "passive"))
      (node (ref "T1") (pin "4") (pinfunction "4_4") (pintype "passive"))
    )
    (net (code "43") (name "Net-(C9-Pad2)") (class "Default")
      (node (ref "C9") (pin "2") (pinfunction "2_2") (pintype "passive"))
      (node (ref "T2") (pin "4") (pinfunction "4_4") (pintype "passive"))
    )
    (net (code "44") (name "Net-(C14-Pad2)") (class "Default")
      (node (ref "C14") (pin "2") (pinfunction "2_2") (pintype "passive"))
      (node (ref "T3") (pin "2") (pinfunction "2_2") (pintype "passive"))
    )
    (net (code "45") (name "Net-(C15-Pad2)") (class "Default")
      (node (ref "C15") (pin "2") (pinfunction "2_2") (pintype "passive"))
      (node (ref "T4") (pin "2") (pinfunction "2_2") (pintype "passive"))
    )
    (net (code "46") (name "Net-(C16-Pad2)") (class "Default")
      (node (ref "C16") (pin "2") (pinfunction "2_2") (pintype "passive"))
      (node (ref "T5") (pin "6") (pinfunction "6_6") (pintype "passive"))
    )
    (net (code "47") (name "Net-(C17-Pad2)") (class "Default")
      (node (ref "C17") (pin "2") (pinfunction "2_2") (pintype "passive"))
      (node (ref "T6") (pin "6") (pinfunction "6_6") (pintype "passive"))
    )
    (net (code "48") (name "Net-(C18-Pad2)") (class "Default")
      (node (ref "C18") (pin "2") (pinfunction "2_2") (pintype "passive"))
      (node (ref "T7") (pin "3") (pinfunction "3_3") (pintype "passive"))
    )
    (net (code "49") (name "Net-(C19-Pad2)") (class "Default")
      (node (ref "C19") (pin "2") (pinfunction "2_2") (pintype "passive"))
      (node (ref "T8") (pin "3") (pinfunction "3_3") (pintype "passive"))
    )
    (net (code "50") (name "Net-(C20-Pad2)") (class "Default")
      (node (ref "C20") (pin "2") (pinfunction "2_2") (pintype "passive"))
      (node (ref "T9") (pin "6") (pinfunction "6_6") (pintype "passive"))
    )
    (net (code "51") (name "Net-(C21-Pad2)") (class "Default")
      (node (ref "C21") (pin "2") (pinfunction "2_2") (pintype "passive"))
      (node (ref "T10") (pin "6") (pinfunction "6_6") (pintype "passive"))
    )
    (net (code "52") (name "Net-(J1-X)") (class "Default")
      (node (ref "C8") (pin "1") (pinfunction "1_1") (pintype "passive"))
      (node (ref "J1") (pin "1") (pinfunction "X_1") (pintype "passive"))
    )
    (net (code "53") (name "Net-(J2-X)") (class "Default")
      (node (ref "C9") (pin "1") (pinfunction "1_1") (pintype "passive"))
      (node (ref "J2") (pin "1") (pinfunction "X_1") (pintype "passive"))
    )
    (net (code "54") (name "Net-(J3-X)") (class "Default")
      (node (ref "C14") (pin "1") (pinfunction "1_1") (pintype "passive"))
      (node (ref "J3") (pin "1") (pinfunction "X_1") (pintype "passive"))
    )
    (net (code "55") (name "Net-(J4-X)") (class "Default")
      (node (ref "C15") (pin "1") (pinfunction "1_1") (pintype "passive"))
      (node (ref "J4") (pin "1") (pinfunction "X_1") (pintype "passive"))
    )
    (net (code "56") (name "Net-(J5-X)") (class "Default")
      (node (ref "C16") (pin "1") (pinfunction "1_1") (pintype "passive"))
      (node (ref "J5") (pin "1") (pinfunction "X_1") (pintype "passive"))
    )
    (net (code "57") (name "Net-(J6-X)") (class "Default")
      (node (ref "C17") (pin "1") (pinfunction "1_1") (pintype "passive"))
      (node (ref "J6") (pin "1") (pinfunction "X_1") (pintype "passive"))
    )
    (net (code "58") (name "Net-(J7-X)") (class "Default")
      (node (ref "C18") (pin "1") (pinfunction "1_1") (pintype "passive"))
      (node (ref "J7") (pin "1") (pinfunction "X_1") (pintype "passive"))
    )
    (net (code "59") (name "Net-(J8-X)") (class "Default")
      (node (ref "C19") (pin "1") (pinfunction "1_1") (pintype "passive"))
      (node (ref "J8") (pin "1") (pinfunction "X_1") (pintype "passive"))
    )
    (net (code "60") (name "Net-(J9-X)") (class "Default")
      (node (ref "C20") (pin "1") (pinfunction "1_1") (pintype "passive"))
      (node (ref "J9") (pin "1") (pinfunction "X_1") (pintype "passive"))
    )
    (net (code "61") (name "Net-(J10-X)") (class "Default")
      (node (ref "C21") (pin "1") (pinfunction "1_1") (pintype "passive"))
      (node (ref "J10") (pin "1") (pinfunction "X_1") (pintype "passive"))
    )
    (net (code "62") (name "Net-(MN1-Pad1)") (class "Default")
      (node (ref "MN1") (pin "1") (pinfunction "1_1") (pintype "passive"))
      (node (ref "MN5") (pin "2") (pinfunction "2_2") (pintype "passive"))
    )
    (net (code "63") (name "Net-(MN2-Pad1)") (class "Default")
      (node (ref "MN2") (pin "1") (pinfunction "1_1") (pintype "passive"))
      (node (ref "MN6") (pin "2") (pinfunction "2_2") (pintype "passive"))
    )
    (net (code "64") (name "Net-(MN3-Pad1)") (class "Default")
      (node (ref "MN3") (pin "1") (pinfunction "1_1") (pintype "passive"))
      (node (ref "MN7") (pin "2") (pinfunction "2_2") (pintype "passive"))
    )
    (net (code "65") (name "Net-(MN4-Pad1)") (class "Default")
      (node (ref "MN4") (pin "1") (pinfunction "1_1") (pintype "passive"))
      (node (ref "MN8") (pin "2") (pinfunction "2_2") (pintype "passive"))
    )
    (net (code "66") (name "Net-(MN17-Pad1)") (class "Default")
      (node (ref "MN17") (pin "1") (pinfunction "1_1") (pintype "passive"))
      (node (ref "MN21") (pin "2") (pinfunction "2_2") (pintype "passive"))
    )
    (net (code "67") (name "Net-(MN18-Pad1)") (class "Default")
      (node (ref "MN18") (pin "1") (pinfunction "1_1") (pintype "passive"))
      (node (ref "MN22") (pin "2") (pinfunction "2_2") (pintype "passive"))
    )
    (net (code "68") (name "Net-(MN19-Pad1)") (class "Default")
      (node (ref "MN19") (pin "1") (pinfunction "1_1") (pintype "passive"))
      (node (ref "MN24") (pin "2") (pinfunction "2_2") (pintype "passive"))
    )
    (net (code "69") (name "Net-(MN20-Pad1)") (class "Default")
      (node (ref "MN20") (pin "1") (pinfunction "1_1") (pintype "passive"))
      (node (ref "MN25") (pin "2") (pinfunction "2_2") (pintype "passive"))
    )
    (net (code "70") (name "VCC1P8_LMS") (class "Default")
      (node (ref "C10") (pin "2") (pinfunction "2_2") (pintype "passive"))
      (node (ref "C11") (pin "2") (pinfunction "2_2") (pintype "passive"))
      (node (ref "C12") (pin "2") (pinfunction "2_2") (pintype "passive"))
      (node (ref "C13") (pin "2") (pinfunction "2_2") (pintype "passive"))
      (node (ref "C4") (pin "2") (pinfunction "2_2") (pintype "passive"))
      (node (ref "C5") (pin "2") (pinfunction "2_2") (pintype "passive"))
      (node (ref "C6") (pin "2") (pinfunction "2_2") (pintype "passive"))
      (node (ref "C7") (pin "2") (pinfunction "2_2") (pintype "passive"))
      (node (ref "MN1") (pin "2") (pinfunction "2_2") (pintype "passive"))
      (node (ref "MN17") (pin "2") (pinfunction "2_2") (pintype "passive"))
      (node (ref "MN18") (pin "2") (pinfunction "2_2") (pintype "passive"))
      (node (ref "MN19") (pin "2") (pinfunction "2_2") (pintype "passive"))
      (node (ref "MN2") (pin "2") (pinfunction "2_2") (pintype "passive"))
      (node (ref "MN20") (pin "2") (pinfunction "2_2") (pintype "passive"))
      (node (ref "MN3") (pin "2") (pinfunction "2_2") (pintype "passive"))
      (node (ref "MN4") (pin "2") (pinfunction "2_2") (pintype "passive"))
    )
  )
)
